# usbasp.net
KiCad netlist of a schematic drawn in EAGLE
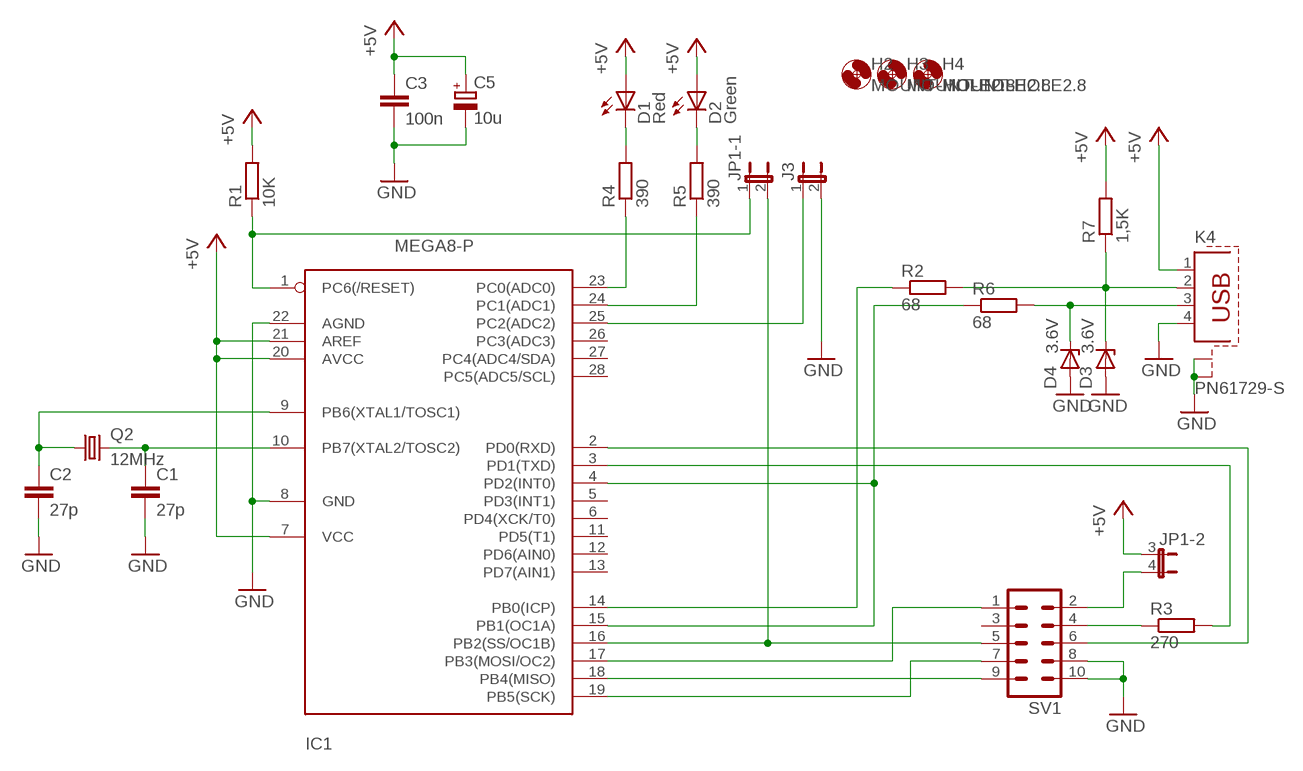
[diagram p0: schematic, sheet 1]

(export (version "E")
  (design (tool "Eeschema 10.0.6"))
  (components
    (comp (ref "C1")
      (value "27p")
      (footprint "eagle-import:C025-024X044")
      (libsource (lib "eagle-import") (part "C-EU025-024X044"))
    )
    (comp (ref "C2")
      (value "27p")
      (footprint "eagle-import:C025-024X044")
      (libsource (lib "eagle-import") (part "C-EU025-024X044"))
    )
    (comp (ref "C3")
      (value "100n")
      (footprint "eagle-import:C5B3")
      (libsource (lib "eagle-import") (part "C5/3"))
    )
    (comp (ref "C5")
      (value "10u")
      (footprint "eagle-import:E2,5-5")
      (libsource (lib "eagle-import") (part "CPOL-EUE2.5-5"))
    )
    (comp (ref "D1")
      (value "Red")
      (footprint "eagle-import:LED5MM")
      (libsource (lib "eagle-import") (part "LED5MM"))
    )
    (comp (ref "D2")
      (value "Green")
      (footprint "eagle-import:LED5MM")
      (libsource (lib "eagle-import") (part "LED5MM"))
    )
    (comp (ref "D3")
      (value "3.6V")
      (footprint "eagle-import:DO34Z7")
      (libsource (lib "eagle-import") (part "ZENER-DIODEDO34-7"))
    )
    (comp (ref "D4")
      (value "3.6V")
      (footprint "eagle-import:DO34Z7")
      (libsource (lib "eagle-import") (part "ZENER-DIODEDO34-7"))
    )
    (comp (ref "H2")
      (value "MOUNT-HOLE2.8")
      (footprint "eagle-import:2,8")
      (libsource (lib "eagle-import") (part "MOUNT-HOLE2.8"))
    )
    (comp (ref "H3")
      (value "MOUNT-HOLE2.8")
      (footprint "eagle-import:2,8")
      (libsource (lib "eagle-import") (part "MOUNT-HOLE2.8"))
    )
    (comp (ref "H4")
      (value "MOUNT-HOLE2.8")
      (footprint "eagle-import:2,8")
      (libsource (lib "eagle-import") (part "MOUNT-HOLE2.8"))
    )
    (comp (ref "IC1")
      (value "MEGA8-P")
      (footprint "eagle-import:DIL28-3")
      (libsource (lib "eagle-import") (part "MEGA8-P"))
    )
    (comp (ref "J3")
      (value "JP1E")
      (footprint "eagle-import:JP1")
      (libsource (lib "eagle-import") (part "JP1E"))
    )
    (comp (ref "JP1")
      (value "JP2QE")
      (footprint "eagle-import:JP2Q")
      (libsource (lib "eagle-import") (part "JP2QE"))
    )
    (comp (ref "K4")
      (value "PN61729-S")
      (footprint "eagle-import:PN61729-S")
      (libsource (lib "eagle-import") (part "PN61729-S"))
    )
    (comp (ref "Q2")
      (value "12MHz")
      (footprint "eagle-import:HC49_S")
      (libsource (lib "eagle-import") (part "CRYSTALHC49S"))
    )
    (comp (ref "R1")
      (value "10K")
      (footprint "eagle-import:0207_10")
      (libsource (lib "eagle-import") (part "R-EU_0207/10"))
    )
    (comp (ref "R2")
      (value "68")
      (footprint "eagle-import:0207_10")
      (libsource (lib "eagle-import") (part "R-EU_0207/10"))
    )
    (comp (ref "R3")
      (value "270")
      (footprint "eagle-import:0207_10")
      (libsource (lib "eagle-import") (part "R-EU_0207/10"))
    )
    (comp (ref "R4")
      (value "390")
      (footprint "eagle-import:0207_10")
      (libsource (lib "eagle-import") (part "R-EU_0207/10"))
    )
    (comp (ref "R5")
      (value "390")
      (footprint "eagle-import:0207_10")
      (libsource (lib "eagle-import") (part "R-EU_0207/10"))
    )
    (comp (ref "R6")
      (value "68")
      (footprint "eagle-import:0207_10")
      (libsource (lib "eagle-import") (part "R-EU_0207/10"))
    )
    (comp (ref "R7")
      (value "1,5K")
      (footprint "eagle-import:0207_10")
      (libsource (lib "eagle-import") (part "R-EU_0207/10"))
    )
    (comp (ref "SV1")
      (value "ML10LANG")
      (footprint "eagle-import:ML10_LANG")
      (libsource (lib "eagle-import") (part "ML10LANG"))
    )
  )
  (nets
    (net (code "1") (name "+5V") (class "Default")
      (node (ref "C3") (pin "1") (pinfunction "1_1") (pintype "passive"))
      (node (ref "C5") (pin "+") (pinfunction "+_+") (pintype "passive"))
      (node (ref "D1") (pin "A") (pinfunction "A_A") (pintype "passive"))
      (node (ref "D2") (pin "A") (pinfunction "A_A") (pintype "passive"))
      (node (ref "IC1") (pin "20") (pinfunction "AVCC_20") (pintype "bidirectional"))
      (node (ref "IC1") (pin "21") (pinfunction "AREF_21") (pintype "bidirectional"))
      (node (ref "IC1") (pin "7") (pinfunction "VCC_7") (pintype "bidirectional"))
      (node (ref "JP1") (pin "3") (pinfunction "1_3") (pintype "passive"))
      (node (ref "K4") (pin "1") (pinfunction "1_1") (pintype "passive"))
      (node (ref "R1") (pin "2") (pinfunction "2_2") (pintype "passive"))
      (node (ref "R7") (pin "2") (pinfunction "2_2") (pintype "passive"))
    )
    (net (code "2") (name "GND") (class "Default")
      (node (ref "C1") (pin "2") (pinfunction "2_2") (pintype "passive"))
      (node (ref "C2") (pin "2") (pinfunction "2_2") (pintype "passive"))
      (node (ref "C3") (pin "2") (pinfunction "2_2") (pintype "passive"))
      (node (ref "C5") (pin "-") (pinfunction "-_-") (pintype "passive"))
      (node (ref "D3") (pin "A") (pinfunction "A_A") (pintype "passive"))
      (node (ref "D4") (pin "A") (pinfunction "A_A") (pintype "passive"))
      (node (ref "IC1") (pin "22") (pinfunction "AGND_22") (pintype "bidirectional"))
      (node (ref "IC1") (pin "8") (pinfunction "GND_8") (pintype "bidirectional"))
      (node (ref "J3") (pin "2") (pinfunction "2_2") (pintype "passive"))
      (node (ref "K4") (pin "4") (pinfunction "4_4") (pintype "passive"))
      (node (ref "K4") (pin "S1") (pinfunction "S1_S1") (pintype "passive"))
      (node (ref "K4") (pin "S2") (pinfunction "S2_S2") (pintype "passive"))
      (node (ref "SV1") (pin "10") (pinfunction "10_10") (pintype "passive"))
      (node (ref "SV1") (pin "8") (pinfunction "8_8") (pintype "passive"))
    )
    (net (code "3") (name "Net-(D1-C)") (class "Default")
      (node (ref "D1") (pin "K") (pinfunction "C_K") (pintype "passive"))
      (node (ref "R4") (pin "2") (pinfunction "2_2") (pintype "passive"))
    )
    (net (code "4") (name "Net-(D2-C)") (class "Default")
      (node (ref "D2") (pin "K") (pinfunction "C_K") (pintype "passive"))
      (node (ref "R5") (pin "2") (pinfunction "2_2") (pintype "passive"))
    )
    (net (code "5") (name "Net-(D3-PadC)") (class "Default")
      (node (ref "D3") (pin "C") (pinfunction "C_C") (pintype "passive"))
      (node (ref "K4") (pin "2") (pinfunction "2_2") (pintype "passive"))
      (node (ref "R2") (pin "2") (pinfunction "2_2") (pintype "passive"))
      (node (ref "R7") (pin "1") (pinfunction "1_1") (pintype "passive"))
    )
    (net (code "6") (name "Net-(D4-PadC)") (class "Default")
      (node (ref "D4") (pin "C") (pinfunction "C_C") (pintype "passive"))
      (node (ref "K4") (pin "3") (pinfunction "3_3") (pintype "passive"))
      (node (ref "R6") (pin "2") (pinfunction "2_2") (pintype "passive"))
    )
    (net (code "7") (name "Net-(IC1-PB0(ICP))") (class "Default")
      (node (ref "IC1") (pin "14") (pinfunction "PB0(ICP)_14") (pintype "bidirectional"))
      (node (ref "R2") (pin "1") (pinfunction "1_1") (pintype "passive"))
    )
    (net (code "8") (name "Net-(IC1-PB1(OC1A))") (class "Default")
      (node (ref "IC1") (pin "15") (pinfunction "PB1(OC1A)_15") (pintype "bidirectional"))
      (node (ref "IC1") (pin "4") (pinfunction "PD2(INT0)_4") (pintype "bidirectional"))
      (node (ref "R6") (pin "1") (pinfunction "1_1") (pintype "passive"))
    )
    (net (code "9") (name "Net-(IC1-PB2(SS{slash}OC1B))") (class "Default")
      (node (ref "IC1") (pin "16") (pinfunction "PB2(SS/OC1B)_16") (pintype "bidirectional"))
      (node (ref "JP1") (pin "2") (pinfunction "2_2") (pintype "passive"))
      (node (ref "SV1") (pin "5") (pinfunction "5_5") (pintype "passive"))
    )
    (net (code "10") (name "Net-(IC1-PB3(MOSI{slash}OC2))") (class "Default")
      (node (ref "IC1") (pin "17") (pinfunction "PB3(MOSI/OC2)_17") (pintype "bidirectional"))
      (node (ref "SV1") (pin "1") (pinfunction "1_1") (pintype "passive"))
    )
    (net (code "11") (name "Net-(IC1-PB4(MISO))") (class "Default")
      (node (ref "IC1") (pin "18") (pinfunction "PB4(MISO)_18") (pintype "bidirectional"))
      (node (ref "SV1") (pin "9") (pinfunction "9_9") (pintype "passive"))
    )
    (net (code "12") (name "Net-(IC1-PB5(SCK))") (class "Default")
      (node (ref "IC1") (pin "19") (pinfunction "PB5(SCK)_19") (pintype "bidirectional"))
      (node (ref "SV1") (pin "7") (pinfunction "7_7") (pintype "passive"))
    )
    (net (code "13") (name "Net-(IC1-PB6(XTAL1{slash}TOSC1))") (class "Default")
      (node (ref "C2") (pin "1") (pinfunction "1_1") (pintype "passive"))
      (node (ref "IC1") (pin "9") (pinfunction "PB6(XTAL1/TOSC1)_9") (pintype "bidirectional"))
      (node (ref "Q2") (pin "1") (pinfunction "1_1") (pintype "passive"))
    )
    (net (code "14") (name "Net-(IC1-PB7(XTAL2{slash}TOSC2))") (class "Default")
      (node (ref "C1") (pin "1") (pinfunction "1_1") (pintype "passive"))
      (node (ref "IC1") (pin "10") (pinfunction "PB7(XTAL2/TOSC2)_10") (pintype "bidirectional"))
      (node (ref "Q2") (pin "2") (pinfunction "2_2") (pintype "passive"))
    )
    (net (code "15") (name "Net-(IC1-PC0(ADC0))") (class "Default")
      (node (ref "IC1") (pin "23") (pinfunction "PC0(ADC0)_23") (pintype "bidirectional"))
      (node (ref "R4") (pin "1") (pinfunction "1_1") (pintype "passive"))
    )
    (net (code "16") (name "Net-(IC1-PC1(ADC1))") (class "Default")
      (node (ref "IC1") (pin "24") (pinfunction "PC1(ADC1)_24") (pintype "bidirectional"))
      (node (ref "R5") (pin "1") (pinfunction "1_1") (pintype "passive"))
    )
    (net (code "17") (name "Net-(IC1-PC2(ADC2))") (class "Default")
      (node (ref "IC1") (pin "25") (pinfunction "PC2(ADC2)_25") (pintype "bidirectional"))
      (node (ref "J3") (pin "1") (pinfunction "1_1") (pintype "passive"))
    )
    (net (code "18") (name "Net-(IC1-PC6({slash}RESET))") (class "Default")
      (node (ref "IC1") (pin "1") (pinfunction "PC6(/RESET)_1") (pintype "bidirectional"))
      (node (ref "JP1") (pin "1") (pinfunction "1_1") (pintype "passive"))
      (node (ref "R1") (pin "1") (pinfunction "1_1") (pintype "passive"))
    )
    (net (code "19") (name "Net-(IC1-PD0(RXD))") (class "Default")
      (node (ref "IC1") (pin "2") (pinfunction "PD0(RXD)_2") (pintype "bidirectional"))
      (node (ref "SV1") (pin "6") (pinfunction "6_6") (pintype "passive"))
    )
    (net (code "20") (name "Net-(IC1-PD1(TXD))") (class "Default")
      (node (ref "IC1") (pin "3") (pinfunction "PD1(TXD)_3") (pintype "bidirectional"))
      (node (ref "R3") (pin "2") (pinfunction "2_2") (pintype "passive"))
    )
    (net (code "21") (name "Net-(JP1B-2)") (class "Default")
      (node (ref "JP1") (pin "4") (pinfunction "2_4") (pintype "passive"))
      (node (ref "SV1") (pin "2") (pinfunction "2_2") (pintype "passive"))
    )
    (net (code "22") (name "Net-(R3-Pad1)") (class "Default")
      (node (ref "R3") (pin "1") (pinfunction "1_1") (pintype "passive"))
      (node (ref "SV1") (pin "4") (pinfunction "4_4") (pintype "passive"))
    )
    (net (code "23") (name "unconnected-(IC1-PC3(ADC3)-Pad26)") (class "Default")
      (node (ref "IC1") (pin "26") (pinfunction "PC3(ADC3)_26") (pintype "bidirectional"))
    )
    (net (code "24") (name "unconnected-(IC1-PC4(ADC4{slash}SDA)-Pad27)") (class "Default")
      (node (ref "IC1") (pin "27") (pinfunction "PC4(ADC4/SDA)_27") (pintype "bidirectional"))
    )
    (net (code "25") (name "unconnected-(IC1-PC5(ADC5{slash}SCL)-Pad28)") (class "Default")
      (node (ref "IC1") (pin "28") (pinfunction "PC5(ADC5/SCL)_28") (pintype "bidirectional"))
    )
    (net (code "26") (name "unconnected-(IC1-PD3(INT1)-Pad5)") (class "Default")
      (node (ref "IC1") (pin "5") (pinfunction "PD3(INT1)_5") (pintype "bidirectional"))
    )
    (net (code "27") (name "unconnected-(IC1-PD4(XCK{slash}T0)-Pad6)") (class "Default")
      (node (ref "IC1") (pin "6") (pinfunction "PD4(XCK/T0)_6") (pintype "bidirectional"))
    )
    (net (code "28") (name "unconnected-(IC1-PD5(T1)-Pad11)") (class "Default")
      (node (ref "IC1") (pin "11") (pinfunction "PD5(T1)_11") (pintype "bidirectional"))
    )
    (net (code "29") (name "unconnected-(IC1-PD6(AIN0)-Pad12)") (class "Default")
      (node (ref "IC1") (pin "12") (pinfunction "PD6(AIN0)_12") (pintype "bidirectional"))
    )
    (net (code "30") (name "unconnected-(IC1-PD7(AIN1)-Pad13)") (class "Default")
      (node (ref "IC1") (pin "13") (pinfunction "PD7(AIN1)_13") (pintype "bidirectional"))
    )
    (net (code "31") (name "unconnected-(SV1-Pad3)") (class "Default")
      (node (ref "SV1") (pin "3") (pinfunction "3_3") (pintype "passive"))
    )
  )
)
